# LAMP.net
KiCad netlist of a schematic drawn in Altium Designer
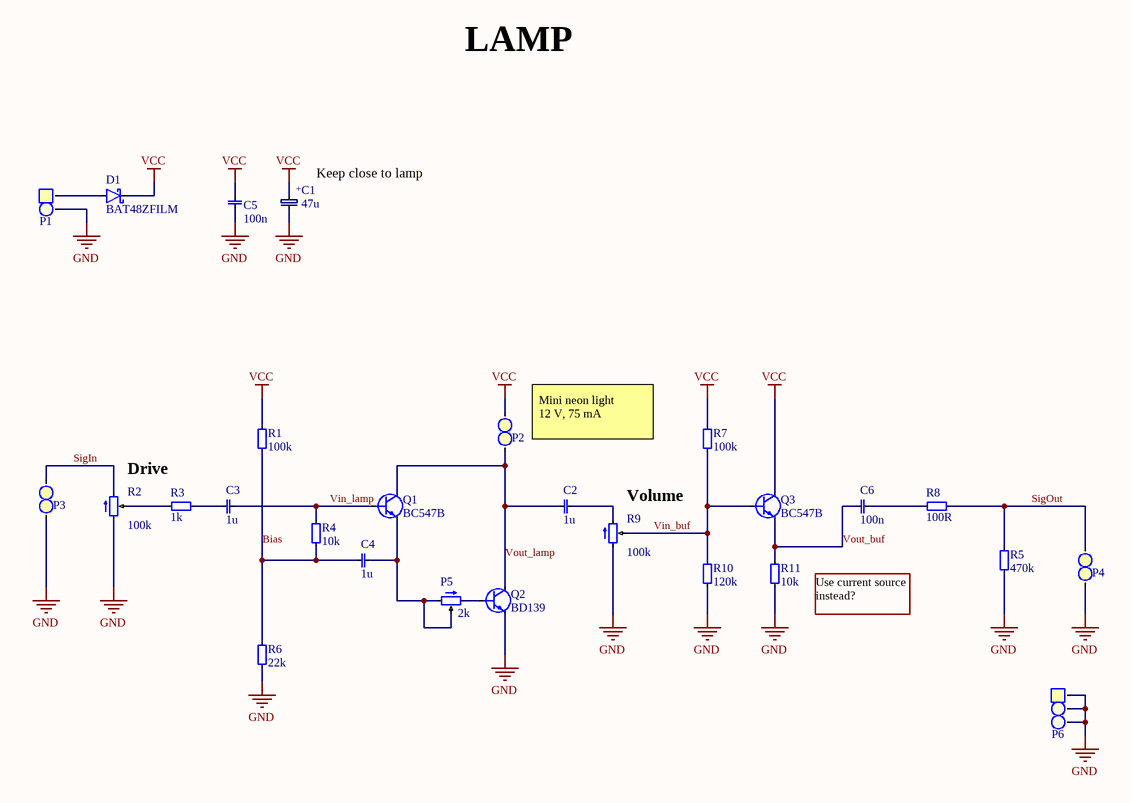
[diagram p0: LAMP.SchDoc]

(export (version "E")
  (design (tool "Eeschema 10.0.6"))
  (components
    (comp (ref "C1")
      (value "47u")
      (footprint "Cap, SMD, Polar, 5.3x5.3mm")
      (description "Capacitor TH 2mm")
      (fields (field (name "Comment") "Capacitor, TH 2mm"))
      (libsource (lib "jclib") (part "Capacitor, TH 2mm"))
    )
    (comp (ref "C2")
      (value "1u")
      (footprint "0805, cap")
      (fields (field (name "Comment") "0805, capacitor"))
      (libsource (lib "jclib") (part "0805, capacitor"))
    )
    (comp (ref "C3")
      (value "1u")
      (footprint "0805, cap")
      (fields (field (name "Comment") "0805, capacitor"))
      (libsource (lib "jclib") (part "0805, capacitor"))
    )
    (comp (ref "C4")
      (value "1u")
      (footprint "0805, cap")
      (fields (field (name "Comment") "0805, capacitor"))
      (libsource (lib "jclib") (part "0805, capacitor"))
    )
    (comp (ref "C5")
      (value "100n")
      (footprint "0805, cap")
      (fields (field (name "Comment") "0805, capacitor"))
      (libsource (lib "jclib") (part "0805, capacitor"))
    )
    (comp (ref "C6")
      (value "100n")
      (footprint "0805, cap")
      (fields (field (name "Comment") "0805, capacitor"))
      (libsource (lib "jclib") (part "0805, capacitor"))
    )
    (comp (ref "D1")
      (value "BAT48ZFILM")
      (footprint "SOD123")
      (description "Rectifier Diode, Schottky, 1 Phase, 1 Element, 0.35A, 40V V(RRM), Silicon")
      (fields (field (name "MANUFACTURER") "STMicroelectronics"))
      (libsource (lib "jclib") (part "BAT48ZFILM"))
    )
    (comp (ref "P1")
      (value "1x2 Pin Header")
      (footprint "padtwo_L")
      (description "2.54 mm, TH")
      (libsource (lib "jclib") (part "1x2 Pin Header"))
    )
    (comp (ref "P2")
      (value "1x2 Pin Heade Straight")
      (footprint "padtwo_L")
      (description "2.54 mm, TH")
      (libsource (lib "jclib") (part "1x2 Pin Heade Straight"))
    )
    (comp (ref "P3")
      (value "1x2 Pin Heade Straight")
      (footprint "padtwo_L")
      (description "2.54 mm, TH")
      (libsource (lib "jclib") (part "1x2 Pin Heade Straight"))
    )
    (comp (ref "P4")
      (value "1x2 Pin Heade Straight")
      (footprint "padtwo_L")
      (description "2.54 mm, TH")
      (libsource (lib "jclib") (part "1x2 Pin Heade Straight"))
    )
    (comp (ref "P5")
      (value "2k")
      (footprint "Pot_3362P")
      (fields (field (name "Comment") "Pot"))
      (libsource (lib "jclib") (part "Pot"))
    )
    (comp (ref "P6")
      (value "1x3 Pin Header")
      (footprint "padThree_L")
      (description "2.54 mm")
      (libsource (lib "jclib") (part "1x3 Pin Header"))
    )
    (comp (ref "Q1")
      (value "BC547B")
      (footprint "BC547_TO-92_BENT")
      (libsource (lib "jclib") (part "NPN CBE"))
    )
    (comp (ref "Q2") (value "BD139") (footprint "TO-126 Angle") (libsource (lib "jclib") (part "NPN ECB")))
    (comp (ref "Q3")
      (value "BC547B")
      (footprint "BC547_TO-92_BENT")
      (libsource (lib "jclib") (part "NPN CBE"))
    )
    (comp (ref "R1")
      (value "100k")
      (footprint "0805")
      (fields (field (name "Comment") "General resistor"))
      (libsource (lib "jclib") (part "resistor"))
    )
    (comp (ref "R2")
      (value "100k")
      (footprint "RK09L_15mm")
      (description "Potentiometer")
      (libsource (lib "jclib") (part "Potentiometer"))
    )
    (comp (ref "R3")
      (value "1k")
      (footprint "0805")
      (fields (field (name "Comment") "General resistor"))
      (libsource (lib "jclib") (part "resistor"))
    )
    (comp (ref "R4")
      (value "10k")
      (footprint "0805")
      (fields (field (name "Comment") "General resistor"))
      (libsource (lib "jclib") (part "resistor"))
    )
    (comp (ref "R5")
      (value "470k")
      (footprint "0805")
      (fields (field (name "Comment") "General resistor"))
      (libsource (lib "jclib") (part "resistor"))
    )
    (comp (ref "R6")
      (value "22k")
      (footprint "0805")
      (fields (field (name "Comment") "General resistor"))
      (libsource (lib "jclib") (part "resistor"))
    )
    (comp (ref "R7")
      (value "100k")
      (footprint "0805")
      (fields (field (name "Comment") "General resistor"))
      (libsource (lib "jclib") (part "resistor"))
    )
    (comp (ref "R8")
      (value "100R")
      (footprint "0805")
      (fields (field (name "Comment") "General resistor"))
      (libsource (lib "jclib") (part "resistor"))
    )
    (comp (ref "R9")
      (value "100k")
      (footprint "RK09L_15mm")
      (description "Potentiometer")
      (libsource (lib "jclib") (part "Potentiometer"))
    )
    (comp (ref "R10")
      (value "120k")
      (footprint "0805")
      (fields (field (name "Comment") "General resistor"))
      (libsource (lib "jclib") (part "resistor"))
    )
    (comp (ref "R11")
      (value "10k")
      (footprint "0805")
      (fields (field (name "Comment") "General resistor"))
      (libsource (lib "jclib") (part "resistor"))
    )
  )
  (nets
    (net (code "1") (name "/Bias") (class "Default")
      (node (ref "C4") (pin "2") (pinfunction "2_2") (pintype "passive"))
      (node (ref "R1") (pin "1") (pinfunction "1_1") (pintype "passive"))
      (node (ref "R4") (pin "1") (pinfunction "1_1") (pintype "passive"))
      (node (ref "R6") (pin "0") (pinfunction "0_0") (pintype "passive"))
    )
    (net (code "2") (name "/SigIn") (class "Default")
      (node (ref "P3") (pin "1") (pinfunction "1_1") (pintype "passive"))
      (node (ref "R2") (pin "3") (pinfunction "3_3") (pintype "passive"))
    )
    (net (code "3") (name "/SigOut") (class "Default")
      (node (ref "P4") (pin "1") (pinfunction "1_1") (pintype "passive"))
      (node (ref "R5") (pin "1") (pinfunction "1_1") (pintype "passive"))
      (node (ref "R8") (pin "0") (pinfunction "0_0") (pintype "passive"))
    )
    (net (code "4") (name "/Vin_buf") (class "Default")
      (node (ref "Q3") (pin "2") (pinfunction "B_2") (pintype "passive"))
      (node (ref "R10") (pin "0") (pinfunction "0_0") (pintype "passive"))
      (node (ref "R7") (pin "1") (pinfunction "1_1") (pintype "passive"))
      (node (ref "R9") (pin "2") (pinfunction "2_2") (pintype "passive"))
    )
    (net (code "5") (name "/Vin_lamp") (class "Default")
      (node (ref "C3") (pin "1") (pinfunction "1_1") (pintype "passive"))
      (node (ref "Q1") (pin "2") (pinfunction "B_2") (pintype "passive"))
      (node (ref "R4") (pin "0") (pinfunction "0_0") (pintype "passive"))
    )
    (net (code "6") (name "/Vout_buf") (class "Default")
      (node (ref "C6") (pin "2") (pinfunction "2_2") (pintype "passive"))
      (node (ref "Q3") (pin "3") (pinfunction "E_3") (pintype "passive"))
      (node (ref "R11") (pin "0") (pinfunction "0_0") (pintype "passive"))
    )
    (net (code "7") (name "/Vout_lamp") (class "Default")
      (node (ref "C2") (pin "2") (pinfunction "2_2") (pintype "passive"))
      (node (ref "P2") (pin "2") (pinfunction "2_2") (pintype "passive"))
      (node (ref "Q1") (pin "1") (pinfunction "C_1") (pintype "passive"))
      (node (ref "Q2") (pin "2") (pinfunction "C_2") (pintype "passive"))
    )
    (net (code "8") (name "GND") (class "Default")
      (node (ref "C1") (pin "1") (pinfunction "1_1") (pintype "passive"))
      (node (ref "C5") (pin "2") (pinfunction "2_2") (pintype "passive"))
      (node (ref "P1") (pin "2") (pinfunction "2_2") (pintype "passive"))
      (node (ref "P3") (pin "2") (pinfunction "2_2") (pintype "passive"))
      (node (ref "P4") (pin "2") (pinfunction "2_2") (pintype "passive"))
      (node (ref "P6") (pin "1") (pinfunction "1_1") (pintype "passive"))
      (node (ref "P6") (pin "2") (pinfunction "2_2") (pintype "passive"))
      (node (ref "P6") (pin "3") (pinfunction "3_3") (pintype "passive"))
      (node (ref "Q2") (pin "1") (pinfunction "E_1") (pintype "passive"))
      (node (ref "R10") (pin "1") (pinfunction "1_1") (pintype "passive"))
      (node (ref "R11") (pin "1") (pinfunction "1_1") (pintype "passive"))
      (node (ref "R2") (pin "1") (pinfunction "1_1") (pintype "passive"))
      (node (ref "R5") (pin "0") (pinfunction "0_0") (pintype "passive"))
      (node (ref "R6") (pin "1") (pinfunction "1_1") (pintype "passive"))
      (node (ref "R9") (pin "1") (pinfunction "1_1") (pintype "passive"))
    )
    (net (code "9") (name "Net-(C2-Pad1)") (class "Default")
      (node (ref "C2") (pin "1") (pinfunction "1_1") (pintype "passive"))
      (node (ref "R9") (pin "3") (pinfunction "3_3") (pintype "passive"))
    )
    (net (code "10") (name "Net-(C3-Pad2)") (class "Default")
      (node (ref "C3") (pin "2") (pinfunction "2_2") (pintype "passive"))
      (node (ref "R3") (pin "1") (pinfunction "1_1") (pintype "passive"))
    )
    (net (code "11") (name "Net-(C6-Pad1)") (class "Default")
      (node (ref "C6") (pin "1") (pinfunction "1_1") (pintype "passive"))
      (node (ref "R8") (pin "1") (pinfunction "1_1") (pintype "passive"))
    )
    (net (code "12") (name "Net-(D1-A)") (class "Default")
      (node (ref "D1") (pin "2") (pinfunction "A_2") (pintype "passive"))
      (node (ref "P1") (pin "1") (pinfunction "1_1") (pintype "passive"))
    )
    (net (code "13") (name "Net-(Q1-E)") (class "Default")
      (node (ref "C4") (pin "1") (pinfunction "1_1") (pintype "passive"))
      (node (ref "P5") (pin "1") (pinfunction "1_1") (pintype "passive"))
      (node (ref "P5") (pin "2") (pinfunction "2_2") (pintype "passive"))
      (node (ref "Q1") (pin "3") (pinfunction "E_3") (pintype "passive"))
    )
    (net (code "14") (name "Net-(Q2-B)") (class "Default")
      (node (ref "P5") (pin "3") (pinfunction "3_3") (pintype "passive"))
      (node (ref "Q2") (pin "3") (pinfunction "B_3") (pintype "passive"))
    )
    (net (code "15") (name "Net-(R2-Pad2)") (class "Default")
      (node (ref "R2") (pin "2") (pinfunction "2_2") (pintype "passive"))
      (node (ref "R3") (pin "0") (pinfunction "0_0") (pintype "passive"))
    )
    (net (code "16") (name "VCC") (class "Default")
      (node (ref "C1") (pin "2") (pinfunction "2_2") (pintype "passive"))
      (node (ref "C5") (pin "1") (pinfunction "1_1") (pintype "passive"))
      (node (ref "D1") (pin "1") (pinfunction "K_1") (pintype "passive"))
      (node (ref "P2") (pin "1") (pinfunction "1_1") (pintype "passive"))
      (node (ref "Q3") (pin "1") (pinfunction "C_1") (pintype "passive"))
      (node (ref "R1") (pin "0") (pinfunction "0_0") (pintype "passive"))
      (node (ref "R7") (pin "0") (pinfunction "0_0") (pintype "passive"))
    )
  )
)
